# kolektorius_v2.net
KiCad netlist of a schematic drawn in EAGLE
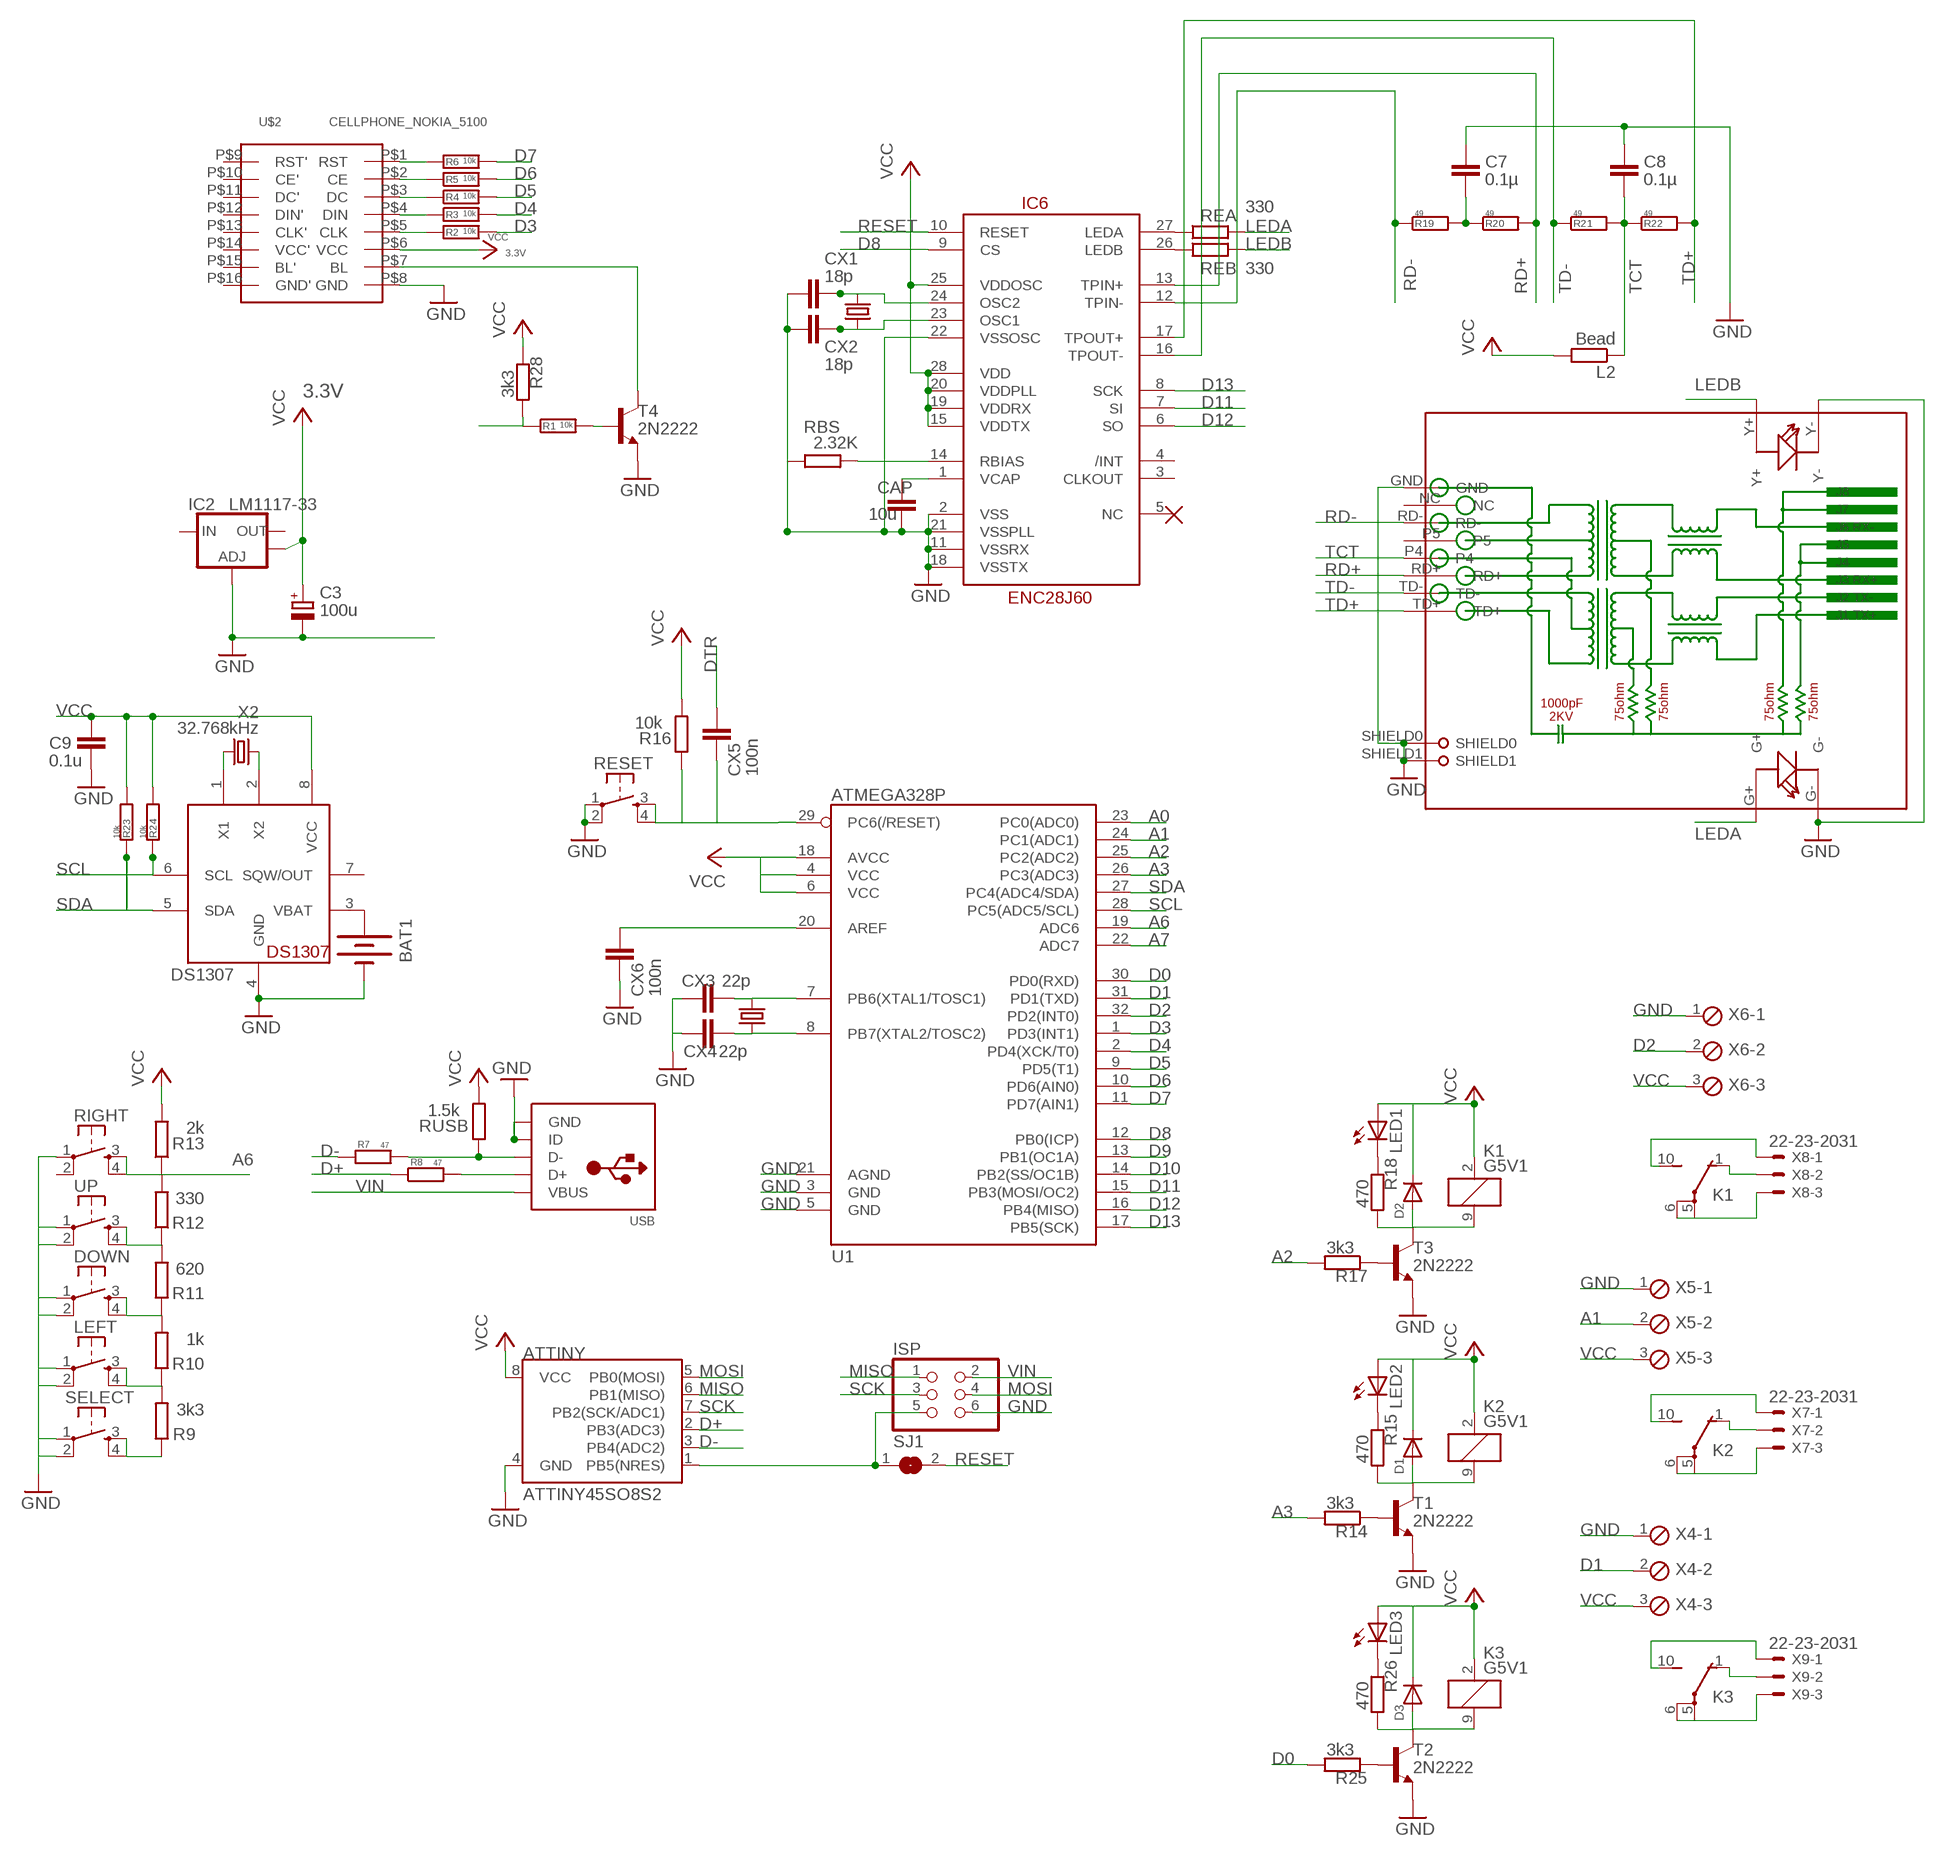
[diagram p0: schematic, sheet 1]

(export (version "E")
  (design (tool "Eeschema 10.0.6"))
  (components
    (comp (ref "ATTINY")
      (value "ATTINY45SO8S2")
      (footprint "eagle-import:SO8S2")
      (libsource (lib "eagle-import") (part "ATTINY45SO8S2"))
    )
    (comp (ref "BAT1")
      (value "BATTERYBATTERY_12MM_SMT")
      (footprint "eagle-import:BATTCON_12MM_SMT")
      (libsource (lib "eagle-import") (part "BATTERYBATTERY_12MM_SMT"))
    )
    (comp (ref "C3")
      (value "100u")
      (footprint "eagle-import:PANASONIC_D")
      (libsource (lib "eagle-import") (part "CPOL-EUD"))
    )
    (comp (ref "C7")
      (value "0.1µ")
      (footprint "eagle-import:C0805")
      (libsource (lib "eagle-import") (part "resistor_C-EUC0805"))
    )
    (comp (ref "C8")
      (value "0.1µ")
      (footprint "eagle-import:C0805")
      (libsource (lib "eagle-import") (part "resistor_C-EUC0805"))
    )
    (comp (ref "C9")
      (value "0.1u")
      (footprint "eagle-import:C0805")
      (libsource (lib "eagle-import") (part "C-EUC0805"))
    )
    (comp (ref "CAP")
      (value "10u")
      (footprint "eagle-import:C0805")
      (libsource (lib "eagle-import") (part "resistor_C-EUC0805"))
    )
    (comp (ref "CX1")
      (value "18p")
      (footprint "eagle-import:C0805")
      (libsource (lib "eagle-import") (part "resistor_C-EUC0805"))
    )
    (comp (ref "CX2")
      (value "18p")
      (footprint "eagle-import:C0805")
      (libsource (lib "eagle-import") (part "resistor_C-EUC0805"))
    )
    (comp (ref "CX3")
      (value "22p")
      (footprint "eagle-import:C0805")
      (libsource (lib "eagle-import") (part "resistor_C-EUC0805"))
    )
    (comp (ref "CX4")
      (value "22p")
      (footprint "eagle-import:C0805")
      (libsource (lib "eagle-import") (part "resistor_C-EUC0805"))
    )
    (comp (ref "CX5")
      (value "100n")
      (footprint "eagle-import:C0805")
      (libsource (lib "eagle-import") (part "resistor_C-EUC0805"))
    )
    (comp (ref "CX6")
      (value "100n")
      (footprint "eagle-import:C0805")
      (libsource (lib "eagle-import") (part "resistor_C-EUC0805"))
    )
    (comp (ref "D1")
      (value "DIODEDO-1N4148")
      (footprint "eagle-import:DO-1N4148")
      (libsource (lib "eagle-import") (part "DIODEDO-1N4148"))
    )
    (comp (ref "D2")
      (value "DIODEDO-1N4148")
      (footprint "eagle-import:DO-1N4148")
      (libsource (lib "eagle-import") (part "DIODEDO-1N4148"))
    )
    (comp (ref "D3")
      (value "DIODEDO-1N4148")
      (footprint "eagle-import:DO-1N4148")
      (libsource (lib "eagle-import") (part "DIODEDO-1N4148"))
    )
    (comp (ref "DOWN")
      (value "TAC_SWITCHPTH")
      (footprint "eagle-import:TACTILE-PTH")
      (libsource (lib "eagle-import") (part "TAC_SWITCHPTH"))
    )
    (comp (ref "DS1307")
      (value "DS1307")
      (footprint "eagle-import:SO08")
      (libsource (lib "eagle-import") (part "DS1307SOIC"))
    )
    (comp (ref "IC2")
      (value "LM1117-33")
      (footprint "eagle-import:SOT223")
      (libsource (lib "eagle-import") (part "V_REG_LM1117SOT223"))
    )
    (comp (ref "IC6")
      (value "ENC28J60")
      (footprint "eagle-import:SSOP28DB")
      (libsource (lib "eagle-import") (part "ENC28J60"))
    )
    (comp (ref "ISP")
      (value "PINHD-2X3")
      (footprint "eagle-import:2X03")
      (libsource (lib "eagle-import") (part "PINHD-2X3"))
    )
    (comp (ref "K1")
      (value "G5V1")
      (footprint "eagle-import:G5V1")
      (fields (field (name "MPN") "G5V-1-DC24"))
      (libsource (lib "eagle-import") (part "G5V1"))
    )
    (comp (ref "K2")
      (value "G5V1")
      (footprint "eagle-import:G5V1")
      (fields (field (name "MPN") "G5V-1-DC24"))
      (libsource (lib "eagle-import") (part "G5V1"))
    )
    (comp (ref "K3")
      (value "G5V1")
      (footprint "eagle-import:G5V1")
      (fields (field (name "MPN") "G5V-1-DC24"))
      (libsource (lib "eagle-import") (part "G5V1"))
    )
    (comp (ref "L2")
      (value "Bead")
      (footprint "eagle-import:R0805")
      (libsource (lib "eagle-import") (part "R-EU_R0805"))
    )
    (comp (ref "LED1")
      (value "LEDSMT1206")
      (footprint "eagle-import:1206")
      (libsource (lib "eagle-import") (part "LEDSMT1206"))
    )
    (comp (ref "LED2")
      (value "LEDSMT1206")
      (footprint "eagle-import:1206")
      (libsource (lib "eagle-import") (part "LEDSMT1206"))
    )
    (comp (ref "LED3")
      (value "LEDSMT1206")
      (footprint "eagle-import:1206")
      (libsource (lib "eagle-import") (part "LEDSMT1206"))
    )
    (comp (ref "LEFT")
      (value "TAC_SWITCHPTH")
      (footprint "eagle-import:TACTILE-PTH")
      (libsource (lib "eagle-import") (part "TAC_SWITCHPTH"))
    )
    (comp (ref "R1")
      (value "10k")
      (footprint "eagle-import:R0805")
      (libsource (lib "eagle-import") (part "R-EU_R0805"))
    )
    (comp (ref "R2")
      (value "10k")
      (footprint "eagle-import:R0805")
      (libsource (lib "eagle-import") (part "R-EU_R0805"))
    )
    (comp (ref "R3")
      (value "10k")
      (footprint "eagle-import:R0805")
      (libsource (lib "eagle-import") (part "R-EU_R0805"))
    )
    (comp (ref "R4")
      (value "10k")
      (footprint "eagle-import:R0805")
      (libsource (lib "eagle-import") (part "R-EU_R0805"))
    )
    (comp (ref "R5")
      (value "10k")
      (footprint "eagle-import:R0805")
      (libsource (lib "eagle-import") (part "R-EU_R0805"))
    )
    (comp (ref "R6")
      (value "10k")
      (footprint "eagle-import:R0805")
      (libsource (lib "eagle-import") (part "R-EU_R0805"))
    )
    (comp (ref "R7")
      (value "47")
      (footprint "eagle-import:R0805")
      (libsource (lib "eagle-import") (part "R-EU_R0805"))
    )
    (comp (ref "R8")
      (value "47")
      (footprint "eagle-import:R0805")
      (libsource (lib "eagle-import") (part "R-EU_R0805"))
    )
    (comp (ref "R9")
      (value "3k3")
      (footprint "eagle-import:R0805")
      (libsource (lib "eagle-import") (part "R-EU_R0805"))
    )
    (comp (ref "R10")
      (value "1k")
      (footprint "eagle-import:R0805")
      (libsource (lib "eagle-import") (part "R-EU_R0805"))
    )
    (comp (ref "R11")
      (value "620")
      (footprint "eagle-import:R0805")
      (libsource (lib "eagle-import") (part "R-EU_R0805"))
    )
    (comp (ref "R12")
      (value "330")
      (footprint "eagle-import:R0805")
      (libsource (lib "eagle-import") (part "R-EU_R0805"))
    )
    (comp (ref "R13")
      (value "2k")
      (footprint "eagle-import:R0805")
      (libsource (lib "eagle-import") (part "R-EU_R0805"))
    )
    (comp (ref "R14")
      (value "3k3")
      (footprint "eagle-import:R0805")
      (libsource (lib "eagle-import") (part "R-EU_R0805"))
    )
    (comp (ref "R15")
      (value "470")
      (footprint "eagle-import:R0805")
      (libsource (lib "eagle-import") (part "R-EU_R0805"))
    )
    (comp (ref "R16")
      (value "10k")
      (footprint "eagle-import:R0805")
      (libsource (lib "eagle-import") (part "R-EU_R0805"))
    )
    (comp (ref "R17")
      (value "3k3")
      (footprint "eagle-import:R0805")
      (libsource (lib "eagle-import") (part "R-EU_R0805"))
    )
    (comp (ref "R18")
      (value "470")
      (footprint "eagle-import:R0805")
      (libsource (lib "eagle-import") (part "R-EU_R0805"))
    )
    (comp (ref "R19")
      (value "49")
      (footprint "eagle-import:R0805")
      (libsource (lib "eagle-import") (part "R-EU_R0805"))
    )
    (comp (ref "R20")
      (value "49")
      (footprint "eagle-import:R0805")
      (libsource (lib "eagle-import") (part "R-EU_R0805"))
    )
    (comp (ref "R21")
      (value "49")
      (footprint "eagle-import:R0805")
      (libsource (lib "eagle-import") (part "R-EU_R0805"))
    )
    (comp (ref "R22")
      (value "49")
      (footprint "eagle-import:R0805")
      (libsource (lib "eagle-import") (part "R-EU_R0805"))
    )
    (comp (ref "R23")
      (value "10k")
      (footprint "eagle-import:R0805")
      (libsource (lib "eagle-import") (part "R-EU_R0805"))
    )
    (comp (ref "R24")
      (value "10k")
      (footprint "eagle-import:R0805")
      (libsource (lib "eagle-import") (part "R-EU_R0805"))
    )
    (comp (ref "R25")
      (value "3k3")
      (footprint "eagle-import:R0805")
      (libsource (lib "eagle-import") (part "R-EU_R0805"))
    )
    (comp (ref "R26")
      (value "470")
      (footprint "eagle-import:R0805")
      (libsource (lib "eagle-import") (part "R-EU_R0805"))
    )
    (comp (ref "R28")
      (value "3k3")
      (footprint "eagle-import:R0805")
      (libsource (lib "eagle-import") (part "R-EU_R0805"))
    )
    (comp (ref "RBS")
      (value "2.32K")
      (footprint "eagle-import:R0805")
      (libsource (lib "eagle-import") (part "R-EU_R0805"))
    )
    (comp (ref "REA")
      (value "330")
      (footprint "eagle-import:R0805")
      (libsource (lib "eagle-import") (part "R-EU_R0805"))
    )
    (comp (ref "REB")
      (value "330")
      (footprint "eagle-import:R0805")
      (libsource (lib "eagle-import") (part "R-EU_R0805"))
    )
    (comp (ref "RESET")
      (value "TAC_SWITCHPTH")
      (footprint "eagle-import:TACTILE-PTH")
      (libsource (lib "eagle-import") (part "TAC_SWITCHPTH"))
    )
    (comp (ref "RIGHT")
      (value "TAC_SWITCHPTH")
      (footprint "eagle-import:TACTILE-PTH")
      (libsource (lib "eagle-import") (part "TAC_SWITCHPTH"))
    )
    (comp (ref "RJ45")
      (value "HR911105A")
      (footprint "eagle-import:HR911105A")
      (libsource (lib "eagle-import") (part "HR911105A"))
    )
    (comp (ref "RUSB")
      (value "1.5k")
      (footprint "eagle-import:R0805")
      (libsource (lib "eagle-import") (part "R-EU_R0805"))
    )
    (comp (ref "SELECT")
      (value "TAC_SWITCHPTH")
      (footprint "eagle-import:TACTILE-PTH")
      (libsource (lib "eagle-import") (part "TAC_SWITCHPTH"))
    )
    (comp (ref "SJ1") (value "SJ") (footprint "eagle-import:SJ") (libsource (lib "eagle-import") (part "SJ")))
    (comp (ref "T1")
      (value "2N2222")
      (footprint "eagle-import:TO92-EBC-OVAL")
      (libsource (lib "eagle-import") (part "2N2222"))
    )
    (comp (ref "T2")
      (value "2N2222")
      (footprint "eagle-import:TO92-EBC-OVAL")
      (libsource (lib "eagle-import") (part "2N2222"))
    )
    (comp (ref "T3")
      (value "2N2222")
      (footprint "eagle-import:TO92-EBC-OVAL")
      (libsource (lib "eagle-import") (part "2N2222"))
    )
    (comp (ref "T4")
      (value "2N2222")
      (footprint "eagle-import:TO92-EBC-OVAL")
      (libsource (lib "eagle-import") (part "2N2222"))
    )
    (comp (ref "U$2")
      (value "CELLPHONE_NOKIA_5100")
      (footprint "eagle-import:CELLPHONE_NOKIA_5100_SPARKFUN")
      (libsource (lib "eagle-import") (part "CELLPHONE_NOKIA_5100"))
    )
    (comp (ref "U1")
      (value "ATMEGA328P")
      (footprint "eagle-import:TQFP32-08")
      (libsource (lib "eagle-import") (part "ATMEGA328_SMT"))
    )
    (comp (ref "UP")
      (value "TAC_SWITCHPTH")
      (footprint "eagle-import:TACTILE-PTH")
      (libsource (lib "eagle-import") (part "TAC_SWITCHPTH"))
    )
    (comp (ref "USB")
      (value "USBMOLEX")
      (footprint "eagle-import:USB-MINIB-THM-MOLEX")
      (libsource (lib "eagle-import") (part "USBMOLEX"))
    )
    (comp (ref "X1")
      (value "25MHz")
      (footprint "eagle-import:HC49US")
      (libsource (lib "eagle-import") (part "CRYSTALHC49US"))
    )
    (comp (ref "X2")
      (value "32.768kHz")
      (footprint "eagle-import:TC26H")
      (libsource (lib "eagle-import") (part "crystal_CRYSTALTC26H"))
    )
    (comp (ref "X3")
      (value "25MHz")
      (footprint "eagle-import:HC49US")
      (libsource (lib "eagle-import") (part "CRYSTALHC49US"))
    )
    (comp (ref "X4")
      (value "MPT3")
      (footprint "eagle-import:3POL254")
      (libsource (lib "eagle-import") (part "MPT3"))
    )
    (comp (ref "X5")
      (value "MPT3")
      (footprint "eagle-import:3POL254")
      (libsource (lib "eagle-import") (part "MPT3"))
    )
    (comp (ref "X6")
      (value "MPT3")
      (footprint "eagle-import:3POL254")
      (libsource (lib "eagle-import") (part "MPT3"))
    )
    (comp (ref "X7")
      (value "22-23-2031")
      (footprint "eagle-import:22-23-2031")
      (fields (field (name "MF") "MOLEX"))
      (libsource (lib "eagle-import") (part "22-23-2031"))
    )
    (comp (ref "X8")
      (value "22-23-2031")
      (footprint "eagle-import:22-23-2031")
      (fields (field (name "MF") "MOLEX"))
      (libsource (lib "eagle-import") (part "22-23-2031"))
    )
    (comp (ref "X9")
      (value "22-23-2031")
      (footprint "eagle-import:22-23-2031")
      (fields (field (name "MF") "MOLEX"))
      (libsource (lib "eagle-import") (part "22-23-2031"))
    )
  )
  (nets
    (net (code "1") (name "/A0") (class "Default")
      (node (ref "U1") (pin "23") (pinfunction "PC0(ADC0)_23") (pintype "bidirectional"))
    )
    (net (code "2") (name "/A1") (class "Default")
      (node (ref "U1") (pin "24") (pinfunction "PC1(ADC1)_24") (pintype "bidirectional"))
      (node (ref "X5") (pin "2") (pinfunction "1_2") (pintype "passive"))
    )
    (net (code "3") (name "/A2") (class "Default")
      (node (ref "R17") (pin "2") (pinfunction "2_2") (pintype "passive"))
      (node (ref "U1") (pin "25") (pinfunction "PC2(ADC2)_25") (pintype "bidirectional"))
    )
    (net (code "4") (name "/A3") (class "Default")
      (node (ref "R14") (pin "2") (pinfunction "2_2") (pintype "passive"))
      (node (ref "U1") (pin "26") (pinfunction "PC3(ADC3)_26") (pintype "bidirectional"))
    )
    (net (code "5") (name "/A6") (class "Default")
      (node (ref "R12") (pin "2") (pinfunction "2_2") (pintype "passive"))
      (node (ref "R13") (pin "1") (pinfunction "1_1") (pintype "passive"))
      (node (ref "RIGHT") (pin "3") (pinfunction "3_3") (pintype "passive"))
      (node (ref "RIGHT") (pin "4") (pinfunction "4_4") (pintype "passive"))
      (node (ref "U1") (pin "19") (pinfunction "ADC6_19") (pintype "bidirectional"))
    )
    (net (code "6") (name "/A7") (class "Default")
      (node (ref "U1") (pin "22") (pinfunction "ADC7_22") (pintype "bidirectional"))
    )
    (net (code "7") (name "/D+") (class "Default")
      (node (ref "ATTINY") (pin "2") (pinfunction "PB3(ADC3)_2") (pintype "bidirectional"))
      (node (ref "R8") (pin "1") (pinfunction "1_1") (pintype "passive"))
    )
    (net (code "8") (name "/D-") (class "Default")
      (node (ref "ATTINY") (pin "3") (pinfunction "PB4(ADC2)_3") (pintype "bidirectional"))
      (node (ref "R7") (pin "1") (pinfunction "1_1") (pintype "passive"))
    )
    (net (code "9") (name "/D0") (class "Default")
      (node (ref "R25") (pin "2") (pinfunction "2_2") (pintype "passive"))
      (node (ref "U1") (pin "30") (pinfunction "PD0(RXD)_30") (pintype "bidirectional"))
    )
    (net (code "10") (name "/D1") (class "Default")
      (node (ref "U1") (pin "31") (pinfunction "PD1(TXD)_31") (pintype "bidirectional"))
      (node (ref "X4") (pin "2") (pinfunction "1_2") (pintype "passive"))
    )
    (net (code "11") (name "/D2") (class "Default")
      (node (ref "U1") (pin "32") (pinfunction "PD2(INT0)_32") (pintype "bidirectional"))
      (node (ref "X6") (pin "2") (pinfunction "1_2") (pintype "passive"))
    )
    (net (code "12") (name "/D3") (class "Default")
      (node (ref "R2") (pin "2") (pinfunction "2_2") (pintype "passive"))
      (node (ref "U1") (pin "1") (pinfunction "PD3(INT1)_1") (pintype "bidirectional"))
    )
    (net (code "13") (name "/D4") (class "Default")
      (node (ref "R3") (pin "2") (pinfunction "2_2") (pintype "passive"))
      (node (ref "U1") (pin "2") (pinfunction "PD4(XCK/T0)_2") (pintype "bidirectional"))
    )
    (net (code "14") (name "/D5") (class "Default")
      (node (ref "R4") (pin "2") (pinfunction "2_2") (pintype "passive"))
      (node (ref "U1") (pin "9") (pinfunction "PD5(T1)_9") (pintype "bidirectional"))
    )
    (net (code "15") (name "/D6") (class "Default")
      (node (ref "R5") (pin "2") (pinfunction "2_2") (pintype "passive"))
      (node (ref "U1") (pin "10") (pinfunction "PD6(AIN0)_10") (pintype "bidirectional"))
    )
    (net (code "16") (name "/D7") (class "Default")
      (node (ref "R6") (pin "2") (pinfunction "2_2") (pintype "passive"))
      (node (ref "U1") (pin "11") (pinfunction "PD7(AIN1)_11") (pintype "bidirectional"))
    )
    (net (code "17") (name "/D8") (class "Default")
      (node (ref "IC6") (pin "9") (pinfunction "CS_9") (pintype "bidirectional"))
      (node (ref "U1") (pin "12") (pinfunction "PB0(ICP)_12") (pintype "bidirectional"))
    )
    (net (code "18") (name "/D9") (class "Default")
      (node (ref "U1") (pin "13") (pinfunction "PB1(OC1A)_13") (pintype "bidirectional"))
    )
    (net (code "19") (name "/D10") (class "Default")
      (node (ref "R1") (pin "1") (pinfunction "1_1") (pintype "passive"))
      (node (ref "R28") (pin "2") (pinfunction "2_2") (pintype "passive"))
      (node (ref "U1") (pin "14") (pinfunction "PB2(SS/OC1B)_14") (pintype "bidirectional"))
    )
    (net (code "20") (name "/D11") (class "Default")
      (node (ref "IC6") (pin "7") (pinfunction "SI_7") (pintype "bidirectional"))
      (node (ref "U1") (pin "15") (pinfunction "PB3(MOSI/OC2)_15") (pintype "bidirectional"))
    )
    (net (code "21") (name "/D12") (class "Default")
      (node (ref "IC6") (pin "6") (pinfunction "SO_6") (pintype "bidirectional"))
      (node (ref "U1") (pin "16") (pinfunction "PB4(MISO)_16") (pintype "bidirectional"))
    )
    (net (code "22") (name "/D13") (class "Default")
      (node (ref "IC6") (pin "8") (pinfunction "SCK_8") (pintype "bidirectional"))
      (node (ref "U1") (pin "17") (pinfunction "PB5(SCK)_17") (pintype "bidirectional"))
    )
    (net (code "23") (name "/DTR") (class "Default")
      (node (ref "CX5") (pin "1") (pinfunction "1_1") (pintype "passive"))
    )
    (net (code "24") (name "/LEDA") (class "Default")
      (node (ref "REA") (pin "2") (pinfunction "2_2") (pintype "passive"))
      (node (ref "RJ45") (pin "G+") (pinfunction "G+_G+") (pintype "bidirectional"))
    )
    (net (code "25") (name "/LEDB") (class "Default")
      (node (ref "REB") (pin "2") (pinfunction "2_2") (pintype "passive"))
      (node (ref "RJ45") (pin "Y+") (pinfunction "Y+_Y+") (pintype "bidirectional"))
    )
    (net (code "26") (name "/MISO") (class "Default")
      (node (ref "ATTINY") (pin "6") (pinfunction "PB1(MISO)_6") (pintype "bidirectional"))
      (node (ref "ISP") (pin "1") (pinfunction "1_1") (pintype "passive"))
    )
    (net (code "27") (name "/MOSI") (class "Default")
      (node (ref "ATTINY") (pin "5") (pinfunction "PB0(MOSI)_5") (pintype "bidirectional"))
      (node (ref "ISP") (pin "4") (pinfunction "4_4") (pintype "passive"))
    )
    (net (code "28") (name "/RD+") (class "Default")
      (node (ref "IC6") (pin "13") (pinfunction "TPIN+_13") (pintype "bidirectional"))
      (node (ref "R20") (pin "2") (pinfunction "2_2") (pintype "passive"))
      (node (ref "RJ45") (pin "RD+") (pinfunction "RD+_RD+") (pintype "bidirectional"))
    )
    (net (code "29") (name "/RD-") (class "Default")
      (node (ref "IC6") (pin "12") (pinfunction "TPIN-_12") (pintype "bidirectional"))
      (node (ref "R19") (pin "1") (pinfunction "1_1") (pintype "passive"))
      (node (ref "RJ45") (pin "RD-") (pinfunction "RD-_RD-") (pintype "bidirectional"))
    )
    (net (code "30") (name "/RESET") (class "Default")
      (node (ref "IC6") (pin "10") (pinfunction "RESET_10") (pintype "bidirectional"))
      (node (ref "SJ1") (pin "2") (pinfunction "2_2") (pintype "passive"))
    )
    (net (code "31") (name "/SCK") (class "Default")
      (node (ref "ATTINY") (pin "7") (pinfunction "PB2(SCK/ADC1)_7") (pintype "bidirectional"))
      (node (ref "ISP") (pin "3") (pinfunction "3_3") (pintype "passive"))
    )
    (net (code "32") (name "/SCL") (class "Default")
      (node (ref "DS1307") (pin "6") (pinfunction "SCL_6") (pintype "bidirectional"))
      (node (ref "R24") (pin "1") (pinfunction "1_1") (pintype "passive"))
      (node (ref "U1") (pin "28") (pinfunction "PC5(ADC5/SCL)_28") (pintype "bidirectional"))
    )
    (net (code "33") (name "/SDA") (class "Default")
      (node (ref "DS1307") (pin "5") (pinfunction "SDA_5") (pintype "bidirectional"))
      (node (ref "R23") (pin "1") (pinfunction "1_1") (pintype "passive"))
      (node (ref "U1") (pin "27") (pinfunction "PC4(ADC4/SDA)_27") (pintype "bidirectional"))
    )
    (net (code "34") (name "/TCT") (class "Default")
      (node (ref "C8") (pin "2") (pinfunction "2_2") (pintype "passive"))
      (node (ref "L2") (pin "1") (pinfunction "1_1") (pintype "passive"))
      (node (ref "R21") (pin "2") (pinfunction "2_2") (pintype "passive"))
      (node (ref "R22") (pin "1") (pinfunction "1_1") (pintype "passive"))
      (node (ref "RJ45") (pin "P4") (pinfunction "P4_P4") (pintype "bidirectional"))
    )
    (net (code "35") (name "/TD+") (class "Default")
      (node (ref "IC6") (pin "17") (pinfunction "TPOUT+_17") (pintype "bidirectional"))
      (node (ref "R22") (pin "2") (pinfunction "2_2") (pintype "passive"))
      (node (ref "RJ45") (pin "TD+") (pinfunction "TD+_TD+") (pintype "bidirectional"))
    )
    (net (code "36") (name "/TD-") (class "Default")
      (node (ref "IC6") (pin "16") (pinfunction "TPOUT-_16") (pintype "bidirectional"))
      (node (ref "R21") (pin "1") (pinfunction "1_1") (pintype "passive"))
      (node (ref "RJ45") (pin "TD-") (pinfunction "TD-_TD-") (pintype "bidirectional"))
    )
    (net (code "37") (name "/VIN") (class "Default")
      (node (ref "ISP") (pin "2") (pinfunction "2_2") (pintype "passive"))
      (node (ref "USB") (pin "VBUS") (pinfunction "VBUS_VBUS") (pintype "power_in"))
    )
    (net (code "38") (name "GND") (class "Default")
      (node (ref "ATTINY") (pin "4") (pinfunction "GND_4") (pintype "bidirectional"))
      (node (ref "BAT1") (pin "P$1") (pinfunction "-_P$1") (pintype "power_in"))
      (node (ref "C3") (pin "-") (pinfunction "-_-") (pintype "passive"))
      (node (ref "C7") (pin "1") (pinfunction "1_1") (pintype "passive"))
      (node (ref "C8") (pin "1") (pinfunction "1_1") (pintype "passive"))
      (node (ref "C9") (pin "2") (pinfunction "2_2") (pintype "passive"))
      (node (ref "CAP") (pin "2") (pinfunction "2_2") (pintype "passive"))
      (node (ref "CX1") (pin "2") (pinfunction "2_2") (pintype "passive"))
      (node (ref "CX2") (pin "2") (pinfunction "2_2") (pintype "passive"))
      (node (ref "CX3") (pin "1") (pinfunction "1_1") (pintype "passive"))
      (node (ref "CX4") (pin "1") (pinfunction "1_1") (pintype "passive"))
      (node (ref "CX6") (pin "2") (pinfunction "2_2") (pintype "passive"))
      (node (ref "DOWN") (pin "1") (pinfunction "1_1") (pintype "passive"))
      (node (ref "DOWN") (pin "2") (pinfunction "2_2") (pintype "passive"))
      (node (ref "DS1307") (pin "4") (pinfunction "GND_4") (pintype "power_in"))
      (node (ref "IC2") (pin "1") (pinfunction "ADJ_1") (pintype "input"))
      (node (ref "IC6") (pin "11") (pinfunction "VSSRX_11") (pintype "bidirectional"))
      (node (ref "IC6") (pin "18") (pinfunction "VSSTX_18") (pintype "bidirectional"))
      (node (ref "IC6") (pin "2") (pinfunction "VSS_2") (pintype "bidirectional"))
      (node (ref "IC6") (pin "21") (pinfunction "VSSPLL_21") (pintype "bidirectional"))
      (node (ref "IC6") (pin "22") (pinfunction "VSSOSC_22") (pintype "bidirectional"))
      (node (ref "ISP") (pin "6") (pinfunction "6_6") (pintype "passive"))
      (node (ref "LEFT") (pin "1") (pinfunction "1_1") (pintype "passive"))
      (node (ref "LEFT") (pin "2") (pinfunction "2_2") (pintype "passive"))
      (node (ref "RBS") (pin "1") (pinfunction "1_1") (pintype "passive"))
      (node (ref "RESET") (pin "1") (pinfunction "1_1") (pintype "passive"))
      (node (ref "RESET") (pin "2") (pinfunction "2_2") (pintype "passive"))
      (node (ref "RIGHT") (pin "1") (pinfunction "1_1") (pintype "passive"))
      (node (ref "RJ45") (pin "G-") (pinfunction "G-_G-") (pintype "bidirectional"))
      (node (ref "RJ45") (pin "GND") (pinfunction "GND_GND") (pintype "bidirectional"))
      (node (ref "RJ45") (pin "SHIELD0") (pinfunction "SHIELD0_SHIELD0") (pintype "bidirectional"))
      (node (ref "RJ45") (pin "SHIELD1") (pinfunction "SHIELD1_SHIELD1") (pintype "bidirectional"))
      (node (ref "RJ45") (pin "Y-") (pinfunction "Y-_Y-") (pintype "bidirectional"))
      (node (ref "SELECT") (pin "1") (pinfunction "1_1") (pintype "passive"))
      (node (ref "SELECT") (pin "2") (pinfunction "2_2") (pintype "passive"))
      (node (ref "T1") (pin "E") (pinfunction "E_E") (pintype "passive"))
      (node (ref "T2") (pin "E") (pinfunction "E_E") (pintype "passive"))
      (node (ref "T3") (pin "E") (pinfunction "E_E") (pintype "passive"))
      (node (ref "T4") (pin "E") (pinfunction "E_E") (pintype "passive"))
      (node (ref "U$2") (pin "P$8") (pinfunction "GND_P$8") (pintype "bidirectional"))
      (node (ref "U1") (pin "21") (pinfunction "AGND_21") (pintype "bidirectional"))
      (node (ref "U1") (pin "3") (pinfunction "GND_3") (pintype "bidirectional"))
      (node (ref "U1") (pin "5") (pinfunction "GND_5") (pintype "bidirectional"))
      (node (ref "UP") (pin "1") (pinfunction "1_1") (pintype "passive"))
      (node (ref "UP") (pin "2") (pinfunction "2_2") (pintype "passive"))
      (node (ref "USB") (pin "GND") (pinfunction "GND_GND") (pintype "power_in"))
      (node (ref "USB") (pin "ID") (pinfunction "ID_ID") (pintype "bidirectional"))
      (node (ref "X4") (pin "1") (pinfunction "1_1") (pintype "passive"))
      (node (ref "X5") (pin "1") (pinfunction "1_1") (pintype "passive"))
      (node (ref "X6") (pin "1") (pinfunction "1_1") (pintype "passive"))
    )
    (net (code "39") (name "Net-(ATTINY-PB5(NRES))") (class "Default")
      (node (ref "ATTINY") (pin "1") (pinfunction "PB5(NRES)_1") (pintype "bidirectional"))
      (node (ref "ISP") (pin "5") (pinfunction "5_5") (pintype "passive"))
      (node (ref "SJ1") (pin "1") (pinfunction "1_1") (pintype "passive"))
    )
    (net (code "40") (name "Net-(BAT1-+)") (class "Default")
      (node (ref "BAT1") (pin "P$2") (pinfunction "+_P$2") (pintype "power_in"))
      (node (ref "DS1307") (pin "3") (pinfunction "VBAT_3") (pintype "power_in"))
    )
    (net (code "41") (name "Net-(C7-Pad2)") (class "Default")
      (node (ref "C7") (pin "2") (pinfunction "2_2") (pintype "passive"))
      (node (ref "R19") (pin "2") (pinfunction "2_2") (pintype "passive"))
      (node (ref "R20") (pin "1") (pinfunction "1_1") (pintype "passive"))
    )
    (net (code "42") (name "Net-(DOWN-Pad3)") (class "Default")
      (node (ref "DOWN") (pin "3") (pinfunction "3_3") (pintype "passive"))
      (node (ref "DOWN") (pin "4") (pinfunction "4_4") (pintype "passive"))
      (node (ref "R10") (pin "2") (pinfunction "2_2") (pintype "passive"))
      (node (ref "R11") (pin "1") (pinfunction "1_1") (pintype "passive"))
    )
    (net (code "43") (name "Net-(DS1307-X1)") (class "Default")
      (node (ref "DS1307") (pin "1") (pinfunction "X1_1") (pintype "passive"))
      (node (ref "X2") (pin "2") (pinfunction "2_2") (pintype "passive"))
    )
    (net (code "44") (name "Net-(DS1307-X2)") (class "Default")
      (node (ref "DS1307") (pin "2") (pinfunction "X2_2") (pintype "passive"))
      (node (ref "X2") (pin "1") (pinfunction "1_1") (pintype "passive"))
    )
    (net (code "45") (name "Net-(IC6-LEDA)") (class "Default")
      (node (ref "IC6") (pin "27") (pinfunction "LEDA_27") (pintype "bidirectional"))
      (node (ref "REA") (pin "1") (pinfunction "1_1") (pintype "passive"))
    )
    (net (code "46") (name "Net-(IC6-LEDB)") (class "Default")
      (node (ref "IC6") (pin "26") (pinfunction "LEDB_26") (pintype "bidirectional"))
      (node (ref "REB") (pin "1") (pinfunction "1_1") (pintype "passive"))
    )
    (net (code "47") (name "Net-(IC6-OSC1)") (class "Default")
      (node (ref "CX2") (pin "1") (pinfunction "1_1") (pintype "passive"))
      (node (ref "IC6") (pin "23") (pinfunction "OSC1_23") (pintype "bidirectional"))
      (node (ref "X1") (pin "1") (pinfunction "1_1") (pintype "passive"))
    )
    (net (code "48") (name "Net-(IC6-OSC2)") (class "Default")
      (node (ref "CX1") (pin "1") (pinfunction "1_1") (pintype "passive"))
      (node (ref "IC6") (pin "24") (pinfunction "OSC2_24") (pintype "bidirectional"))
      (node (ref "X1") (pin "2") (pinfunction "2_2") (pintype "passive"))
    )
    (net (code "49") (name "Net-(IC6-RBIAS)") (class "Default")
      (node (ref "IC6") (pin "14") (pinfunction "RBIAS_14") (pintype "bidirectional"))
      (node (ref "RBS") (pin "2") (pinfunction "2_2") (pintype "passive"))
    )
    (net (code "50") (name "Net-(IC6-VCAP)") (class "Default")
      (node (ref "CAP") (pin "1") (pinfunction "1_1") (pintype "passive"))
      (node (ref "IC6") (pin "1") (pinfunction "VCAP_1") (pintype "bidirectional"))
    )
    (net (code "51") (name "Net-(K1A-2)") (class "Default")
      (node (ref "D2") (pin "A") (pinfunction "A_A") (pintype "passive"))
      (node (ref "K1") (pin "9") (pinfunction "2_9") (pintype "passive"))
      (node (ref "R18") (pin "2") (pinfunction "2_2") (pintype "passive"))
      (node (ref "T3") (pin "C") (pinfunction "C_C") (pintype "passive"))
    )
    (net (code "52") (name "Net-(K1B-O)") (class "Default")
      (node (ref "K1") (pin "1") (pinfunction "O_1") (pintype "passive"))
      (node (ref "X8") (pin "2") (pinfunction "S_2") (pintype "passive"))
    )
    (net (code "53") (name "Net-(K1B-S)") (class "Default")
      (node (ref "K1") (pin "10") (pinfunction "S_10") (pintype "passive"))
      (node (ref "X8") (pin "1") (pinfunction "S_1") (pintype "passive"))
    )
    (net (code "54") (name "Net-(K2A-2)") (class "Default")
      (node (ref "D1") (pin "A") (pinfunction "A_A") (pintype "passive"))
      (node (ref "K2") (pin "9") (pinfunction "2_9") (pintype "passive"))
      (node (ref "R15") (pin "2") (pinfunction "2_2") (pintype "passive"))
      (node (ref "T1") (pin "C") (pinfunction "C_C") (pintype "passive"))
    )
    (net (code "55") (name "Net-(K2B-O)") (class "Default")
      (node (ref "K2") (pin "1") (pinfunction "O_1") (pintype "passive"))
      (node (ref "X7") (pin "2") (pinfunction "S_2") (pintype "passive"))
    )
    (net (code "56") (name "Net-(K2B-S)") (class "Default")
      (node (ref "K2") (pin "10") (pinfunction "S_10") (pintype "passive"))
      (node (ref "X7") (pin "1") (pinfunction "S_1") (pintype "passive"))
    )
    (net (code "57") (name "Net-(K3A-2)") (class "Default")
      (node (ref "D3") (pin "A") (pinfunction "A_A") (pintype "passive"))
      (node (ref "K3") (pin "9") (pinfunction "2_9") (pintype "passive"))
      (node (ref "R26") (pin "2") (pinfunction "2_2") (pintype "passive"))
      (node (ref "T2") (pin "C") (pinfunction "C_C") (pintype "passive"))
    )
    (net (code "58") (name "Net-(K3B-O)") (class "Default")
      (node (ref "K3") (pin "1") (pinfunction "O_1") (pintype "passive"))
      (node (ref "X9") (pin "2") (pinfunction "S_2") (pintype "passive"))
    )
    (net (code "59") (name "Net-(K3B-S)") (class "Default")
      (node (ref "K3") (pin "10") (pinfunction "S_10") (pintype "passive"))
      (node (ref "X9") (pin "1") (pinfunction "S_1") (pintype "passive"))
    )
    (net (code "60") (name "Net-(LED1-PadC)") (class "Default")
      (node (ref "LED1") (pin "C") (pinfunction "C_C") (pintype "passive"))
      (node (ref "R18") (pin "1") (pinfunction "1_1") (pintype "passive"))
    )
    (net (code "61") (name "Net-(LED2-PadC)") (class "Default")
      (node (ref "LED2") (pin "C") (pinfunction "C_C") (pintype "passive"))
      (node (ref "R15") (pin "1") (pinfunction "1_1") (pintype "passive"))
    )
    (net (code "62") (name "Net-(LED3-PadC)") (class "Default")
      (node (ref "LED3") (pin "C") (pinfunction "C_C") (pintype "passive"))
      (node (ref "R26") (pin "1") (pinfunction "1_1") (pintype "passive"))
    )
    (net (code "63") (name "Net-(LEFT-Pad3)") (class "Default")
      (node (ref "LEFT") (pin "3") (pinfunction "3_3") (pintype "passive"))
      (node (ref "LEFT") (pin "4") (pinfunction "4_4") (pintype "passive"))
      (node (ref "R10") (pin "1") (pinfunction "1_1") (pintype "passive"))
      (node (ref "R9") (pin "2") (pinfunction "2_2") (pintype "passive"))
    )
    (net (code "64") (name "Net-(R1-Pad2)") (class "Default")
      (node (ref "R1") (pin "2") (pinfunction "2_2") (pintype "passive"))
      (node (ref "T4") (pin "B") (pinfunction "B_B") (pintype "passive"))
    )
    (net (code "65") (name "Net-(R7-Pad2)") (class "Default")
      (node (ref "R7") (pin "2") (pinfunction "2_2") (pintype "passive"))
      (node (ref "RUSB") (pin "1") (pinfunction "1_1") (pintype "passive"))
      (node (ref "USB") (pin "D-") (pinfunction "D-_D-") (pintype "bidirectional"))
    )
    (net (code "66") (name "Net-(R8-Pad2)") (class "Default")
      (node (ref "R8") (pin "2") (pinfunction "2_2") (pintype "passive"))
      (node (ref "USB") (pin "D+") (pinfunction "D+_D+") (pintype "bidirectional"))
    )
    (net (code "67") (name "Net-(R9-Pad1)") (class "Default")
      (node (ref "R9") (pin "1") (pinfunction "1_1") (pintype "passive"))
      (node (ref "SELECT") (pin "3") (pinfunction "3_3") (pintype "passive"))
      (node (ref "SELECT") (pin "4") (pinfunction "4_4") (pintype "passive"))
    )
    (net (code "68") (name "Net-(R11-Pad2)") (class "Default")
      (node (ref "R11") (pin "2") (pinfunction "2_2") (pintype "passive"))
      (node (ref "R12") (pin "1") (pinfunction "1_1") (pintype "passive"))
      (node (ref "UP") (pin "3") (pinfunction "3_3") (pintype "passive"))
      (node (ref "UP") (pin "4") (pinfunction "4_4") (pintype "passive"))
    )
    (net (code "69") (name "Net-(R14-Pad1)") (class "Default")
      (node (ref "R14") (pin "1") (pinfunction "1_1") (pintype "passive"))
      (node (ref "T1") (pin "B") (pinfunction "B_B") (pintype "passive"))
    )
    (net (code "70") (name "Net-(R17-Pad1)") (class "Default")
      (node (ref "R17") (pin "1") (pinfunction "1_1") (pintype "passive"))
      (node (ref "T3") (pin "B") (pinfunction "B_B") (pintype "passive"))
    )
    (net (code "71") (name "Net-(R25-Pad1)") (class "Default")
      (node (ref "R25") (pin "1") (pinfunction "1_1") (pintype "passive"))
      (node (ref "T2") (pin "B") (pinfunction "B_B") (pintype "passive"))
    )
    (net (code "72") (name "Net-(U$2-BL)") (class "Default")
      (node (ref "T4") (pin "C") (pinfunction "C_C") (pintype "passive"))
      (node (ref "U$2") (pin "P$7") (pinfunction "BL_P$7") (pintype "bidirectional"))
    )
    (net (code "73") (name "Net-(U$2-CE)") (class "Default")
      (node (ref "R5") (pin "1") (pinfunction "1_1") (pintype "passive"))
      (node (ref "U$2") (pin "P$2") (pinfunction "CE_P$2") (pintype "bidirectional"))
    )
    (net (code "74") (name "Net-(U$2-CLK)") (class "Default")
      (node (ref "R2") (pin "1") (pinfunction "1_1") (pintype "passive"))
      (node (ref "U$2") (pin "P$5") (pinfunction "CLK_P$5") (pintype "bidirectional"))
    )
    (net (code "75") (name "Net-(U$2-DC)") (class "Default")
      (node (ref "R4") (pin "1") (pinfunction "1_1") (pintype "passive"))
      (node (ref "U$2") (pin "P$3") (pinfunction "DC_P$3") (pintype "bidirectional"))
    )
    (net (code "76") (name "Net-(U$2-DIN)") (class "Default")
      (node (ref "R3") (pin "1") (pinfunction "1_1") (pintype "passive"))
      (node (ref "U$2") (pin "P$4") (pinfunction "DIN_P$4") (pintype "bidirectional"))
    )
    (net (code "77") (name "Net-(U$2-RST)") (class "Default")
      (node (ref "R6") (pin "1") (pinfunction "1_1") (pintype "passive"))
      (node (ref "U$2") (pin "P$1") (pinfunction "RST_P$1") (pintype "bidirectional"))
    )
    (net (code "78") (name "Net-(U1-AREF)") (class "Default")
      (node (ref "CX6") (pin "1") (pinfunction "1_1") (pintype "passive"))
      (node (ref "U1") (pin "20") (pinfunction "AREF_20") (pintype "bidirectional"))
    )
    (net (code "79") (name "Net-(U1-PB6(XTAL1{slash}TOSC1))") (class "Default")
      (node (ref "CX3") (pin "2") (pinfunction "2_2") (pintype "passive"))
      (node (ref "U1") (pin "7") (pinfunction "PB6(XTAL1/TOSC1)_7") (pintype "bidirectional"))
      (node (ref "X3") (pin "2") (pinfunction "2_2") (pintype "passive"))
    )
    (net (code "80") (name "Net-(U1-PB7(XTAL2{slash}TOSC2))") (class "Default")
      (node (ref "CX4") (pin "2") (pinfunction "2_2") (pintype "passive"))
      (node (ref "U1") (pin "8") (pinfunction "PB7(XTAL2/TOSC2)_8") (pintype "bidirectional"))
      (node (ref "X3") (pin "1") (pinfunction "1_1") (pintype "passive"))
    )
    (net (code "81") (name "Net-(U1-PC6({slash}RESET))") (class "Default")
      (node (ref "CX5") (pin "2") (pinfunction "2_2") (pintype "passive"))
      (node (ref "R16") (pin "1") (pinfunction "1_1") (pintype "passive"))
      (node (ref "RESET") (pin "3") (pinfunction "3_3") (pintype "passive"))
      (node (ref "RESET") (pin "4") (pinfunction "4_4") (pintype "passive"))
      (node (ref "U1") (pin "29") (pinfunction "PC6(/RESET)_29") (pintype "bidirectional"))
    )
    (net (code "82") (name "Net-(X7C-S)") (class "Default")
      (node (ref "K2") (pin "5") (pinfunction "P_5") (pintype "passive"))
      (node (ref "K2") (pin "6") (pinfunction "P_6") (pintype "passive"))
      (node (ref "X7") (pin "3") (pinfunction "S_3") (pintype "passive"))
    )
    (net (code "83") (name "Net-(X8C-S)") (class "Default")
      (node (ref "K1") (pin "5") (pinfunction "P_5") (pintype "passive"))
      (node (ref "K1") (pin "6") (pinfunction "P_6") (pintype "passive"))
      (node (ref "X8") (pin "3") (pinfunction "S_3") (pintype "passive"))
    )
    (net (code "84") (name "Net-(X9C-S)") (class "Default")
      (node (ref "K3") (pin "5") (pinfunction "P_5") (pintype "passive"))
      (node (ref "K3") (pin "6") (pinfunction "P_6") (pintype "passive"))
      (node (ref "X9") (pin "3") (pinfunction "S_3") (pintype "passive"))
    )
    (net (code "85") (name "VCC") (class "Default")
      (node (ref "ATTINY") (pin "8") (pinfunction "VCC_8") (pintype "bidirectional"))
      (node (ref "C3") (pin "+") (pinfunction "+_+") (pintype "passive"))
      (node (ref "C9") (pin "1") (pinfunction "1_1") (pintype "passive"))
      (node (ref "D1") (pin "C") (pinfunction "C_C") (pintype "passive"))
      (node (ref "D2") (pin "C") (pinfunction "C_C") (pintype "passive"))
      (node (ref "D3") (pin "C") (pinfunction "C_C") (pintype "passive"))
      (node (ref "DS1307") (pin "8") (pinfunction "VCC_8") (pintype "power_in"))
      (node (ref "IC2") (pin "4") (pinfunction "OUT_4") (pintype "bidirectional"))
      (node (ref "IC6") (pin "15") (pinfunction "VDDTX_15") (pintype "bidirectional"))
      (node (ref "IC6") (pin "19") (pinfunction "VDDRX_19") (pintype "bidirectional"))
      (node (ref "IC6") (pin "20") (pinfunction "VDDPLL_20") (pintype "bidirectional"))
      (node (ref "IC6") (pin "25") (pinfunction "VDDOSC_25") (pintype "bidirectional"))
      (node (ref "IC6") (pin "28") (pinfunction "VDD_28") (pintype "bidirectional"))
      (node (ref "K1") (pin "2") (pinfunction "1_2") (pintype "passive"))
      (node (ref "K2") (pin "2") (pinfunction "1_2") (pintype "passive"))
      (node (ref "K3") (pin "2") (pinfunction "1_2") (pintype "passive"))
      (node (ref "L2") (pin "2") (pinfunction "2_2") (pintype "passive"))
      (node (ref "LED1") (pin "A") (pinfunction "A_A") (pintype "passive"))
      (node (ref "LED2") (pin "A") (pinfunction "A_A") (pintype "passive"))
      (node (ref "LED3") (pin "A") (pinfunction "A_A") (pintype "passive"))
      (node (ref "R13") (pin "2") (pinfunction "2_2") (pintype "passive"))
      (node (ref "R16") (pin "2") (pinfunction "2_2") (pintype "passive"))
      (node (ref "R23") (pin "2") (pinfunction "2_2") (pintype "passive"))
      (node (ref "R24") (pin "2") (pinfunction "2_2") (pintype "passive"))
      (node (ref "R28") (pin "1") (pinfunction "1_1") (pintype "passive"))
      (node (ref "RUSB") (pin "2") (pinfunction "2_2") (pintype "passive"))
      (node (ref "U$2") (pin "P$6") (pinfunction "VCC_P$6") (pintype "bidirectional"))
      (node (ref "U1") (pin "18") (pinfunction "AVCC_18") (pintype "bidirectional"))
      (node (ref "U1") (pin "4") (pinfunction "VCC_4") (pintype "bidirectional"))
      (node (ref "U1") (pin "6") (pinfunction "VCC_6") (pintype "bidirectional"))
      (node (ref "X4") (pin "3") (pinfunction "1_3") (pintype "passive"))
      (node (ref "X5") (pin "3") (pinfunction "1_3") (pintype "passive"))
      (node (ref "X6") (pin "3") (pinfunction "1_3") (pintype "passive"))
    )
    (net (code "86") (name "unconnected-(DS1307-SQW{slash}OUT-Pad7)") (class "Default")
      (node (ref "DS1307") (pin "7") (pinfunction "SQW/OUT_7") (pintype "bidirectional"))
    )
    (net (code "87") (name "unconnected-(IC2-IN-Pad3)") (class "Default")
      (node (ref "IC2") (pin "3") (pinfunction "IN_3") (pintype "input"))
    )
    (net (code "88") (name "unconnected-(IC2-OUT-Pad2)") (class "Default")
      (node (ref "IC2") (pin "2") (pinfunction "OUT_2") (pintype "bidirectional"))
    )
    (net (code "89") (name "unconnected-(IC6-CLKOUT-Pad3)") (class "Default")
      (node (ref "IC6") (pin "3") (pinfunction "CLKOUT_3") (pintype "bidirectional"))
    )
    (net (code "90") (name "unconnected-(IC6-NC-Pad5)") (class "Default")
      (node (ref "IC6") (pin "5") (pinfunction "NC_5") (pintype "bidirectional"))
    )
    (net (code "91") (name "unconnected-(IC6-{slash}INT-Pad4)") (class "Default")
      (node (ref "IC6") (pin "4") (pinfunction "/INT_4") (pintype "bidirectional"))
    )
    (net (code "92") (name "unconnected-(RIGHT-Pad2)") (class "Default")
      (node (ref "RIGHT") (pin "2") (pinfunction "2_2") (pintype "passive"))
    )
    (net (code "93") (name "unconnected-(RJ45-PadNC)") (class "Default")
      (node (ref "RJ45") (pin "NC") (pinfunction "NC_NC") (pintype "bidirectional"))
    )
    (net (code "94") (name "unconnected-(RJ45-PadP5)") (class "Default")
      (node (ref "RJ45") (pin "P5") (pinfunction "P5_P5") (pintype "bidirectional"))
    )
    (net (code "95") (name "unconnected-(U$2-BL'-PadP$15)") (class "Default")
      (node (ref "U$2") (pin "P$15") (pinfunction "BL'_P$15") (pintype "bidirectional"))
    )
    (net (code "96") (name "unconnected-(U$2-CE'-PadP$10)") (class "Default")
      (node (ref "U$2") (pin "P$10") (pinfunction "CE'_P$10") (pintype "bidirectional"))
    )
    (net (code "97") (name "unconnected-(U$2-CLK'-PadP$13)") (class "Default")
      (node (ref "U$2") (pin "P$13") (pinfunction "CLK'_P$13") (pintype "bidirectional"))
    )
    (net (code "98") (name "unconnected-(U$2-DC'-PadP$11)") (class "Default")
      (node (ref "U$2") (pin "P$11") (pinfunction "DC'_P$11") (pintype "bidirectional"))
    )
    (net (code "99") (name "unconnected-(U$2-DIN'-PadP$12)") (class "Default")
      (node (ref "U$2") (pin "P$12") (pinfunction "DIN'_P$12") (pintype "bidirectional"))
    )
    (net (code "100") (name "unconnected-(U$2-GND'-PadP$16)") (class "Default")
      (node (ref "U$2") (pin "P$16") (pinfunction "GND'_P$16") (pintype "bidirectional"))
    )
    (net (code "101") (name "unconnected-(U$2-RST'-PadP$9)") (class "Default")
      (node (ref "U$2") (pin "P$9") (pinfunction "RST'_P$9") (pintype "bidirectional"))
    )
    (net (code "102") (name "unconnected-(U$2-VCC'-PadP$14)") (class "Default")
      (node (ref "U$2") (pin "P$14") (pinfunction "VCC'_P$14") (pintype "bidirectional"))
    )
  )
)
